# Digital-input.net
KiCad netlist of a schematic drawn in Altium Designer
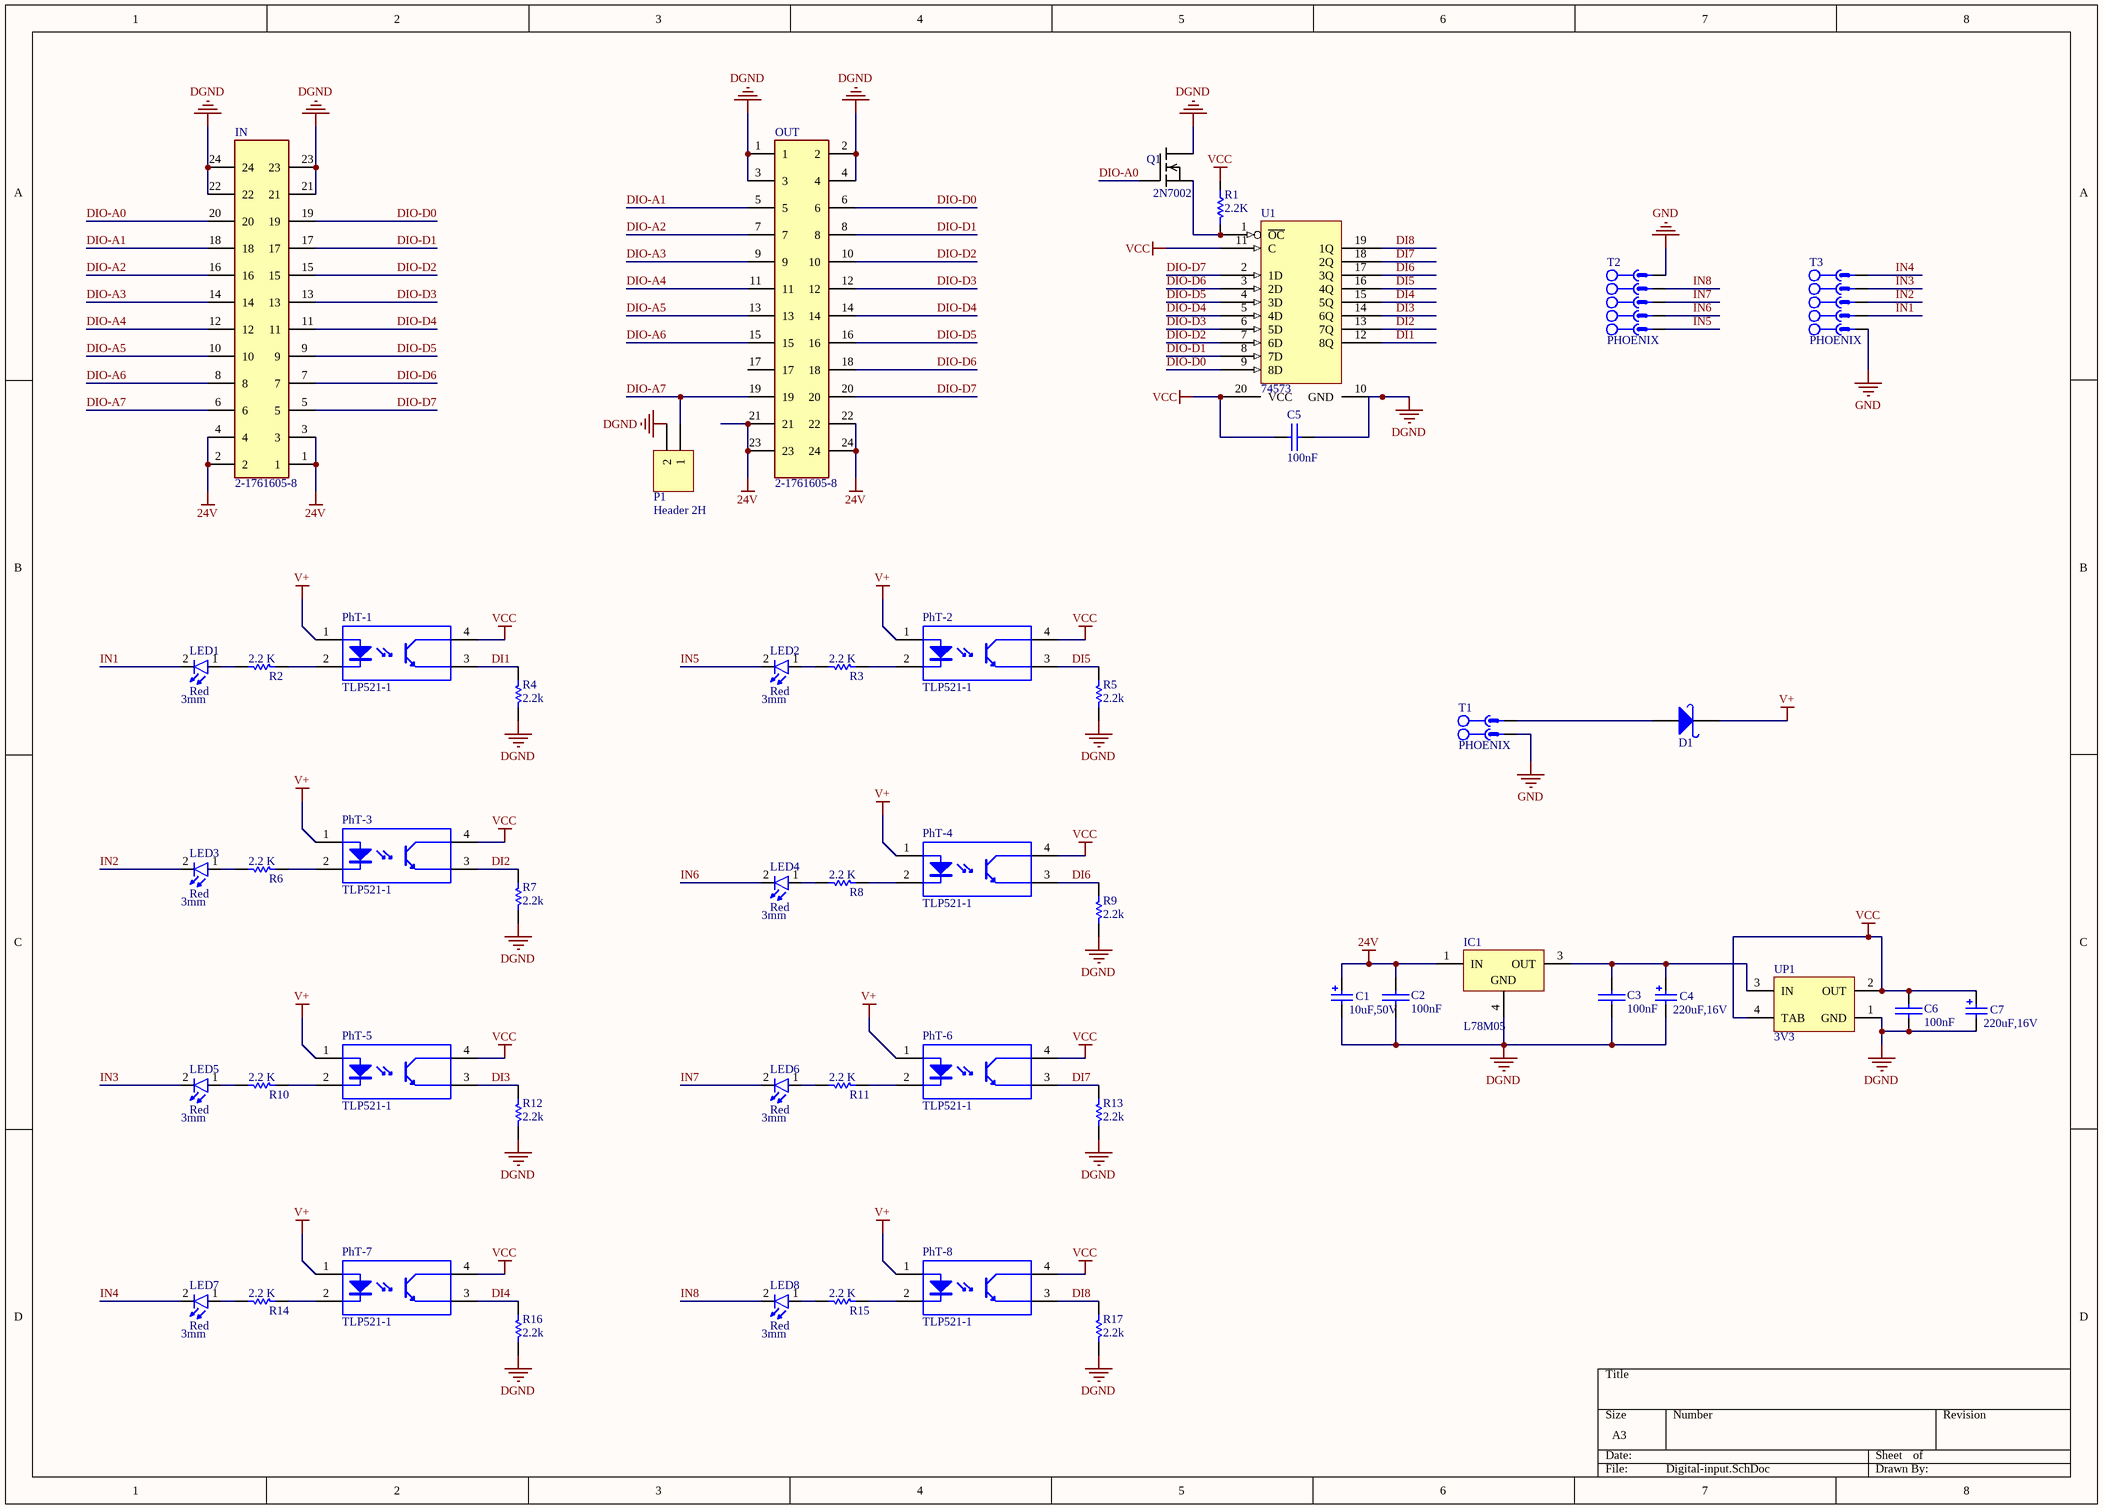
[diagram p0: Digital-input.SchDoc]

(export (version "E")
  (design (tool "Eeschema 10.0.6"))
  (components
    (comp (ref "C1")
      (value "10uF,50V")
      (footprint "WCAP-AS5H_6.3x7.7")
      (description "WCAP-AS5H SMT Aluminum Electrolytic Capacitors, D8mm x L10.5mm, 47uF, +/-20%, 50VDC")
      (fields (field (name "PART NUMBER") "865230653012") (field (name "PUBLISHER") "Wurth Elektronik"))
      (libsource (lib "Altium_WCAP-AS5H (rev19a)") (part "865230653012"))
    )
    (comp (ref "C2")
      (value "100nF")
      (footprint "SMD_CAP_0805")
      (description "Bipolar Capacitor")
      (fields (field (name "VOLTAGE") "100V") (field (name "DESIGNER") "Saeid Jorablo"))
      (libsource (lib "My_Library") (part "Cap-Bipolar"))
    )
    (comp (ref "C3")
      (value "100nF")
      (footprint "SMD_CAP_0805")
      (description "Bipolar Capacitor")
      (fields (field (name "VOLTAGE") "100V") (field (name "DESIGNER") "Saeid Jorablo"))
      (libsource (lib "My_Library") (part "Cap-Bipolar"))
    )
    (comp (ref "C4")
      (value "220uF,16V")
      (footprint "WCAP-AS5H_6.3x7.7")
      (description "WCAP-AS5H SMT Aluminum Electrolytic Capacitors, D6.3mm x L7.7mm, 100uF, +/-20%, 16VDC")
      (fields (field (name "PART NUMBER") "865230345005") (field (name "PUBLISHER") "Wurth Elektronik"))
      (libsource (lib "Altium_WCAP-AS5H (rev19a)") (part "865230345005"))
    )
    (comp (ref "C5")
      (value "100nF")
      (footprint "SMD_CAP_0805")
      (description "Bipolar Capacitor")
      (fields (field (name "VOLTAGE") "100V") (field (name "DESIGNER") "Saeid Jorablo"))
      (libsource (lib "My_Library") (part "Cap-Bipolar"))
    )
    (comp (ref "C6")
      (value "100nF")
      (footprint "SMD_CAP_0805")
      (description "Bipolar Capacitor")
      (fields (field (name "VOLTAGE") "100V") (field (name "DESIGNER") "Saeid Jorablo"))
      (libsource (lib "My_Library") (part "Cap-Bipolar"))
    )
    (comp (ref "C7")
      (value "220uF,16V")
      (footprint "WCAP-AS5H_6.3x7.7")
      (description "WCAP-AS5H SMT Aluminum Electrolytic Capacitors, D6.3mm x L7.7mm, 100uF, +/-20%, 16VDC")
      (fields (field (name "PART NUMBER") "865230345005") (field (name "PUBLISHER") "Wurth Elektronik"))
      (libsource (lib "Altium_WCAP-AS5H (rev19a)") (part "865230345005"))
    )
    (comp (ref "D1")
      (value "1n5822")
      (footprint "Diode 1N4007 SMD")
      (description "Schottky Rectifiers")
      (fields
        (field (name "MANUFACTURER") "ON Semiconductor/Fairchild")
        (field (name "DESIGNER") "Abbas Basereh")
      )
      (libsource (lib "Altium") (part "1N5822 SMD"))
    )
    (comp (ref "IC1")
      (value "L78M05")
      (footprint "TO-252")
      (description "Precision 500mA Regulator")
      (libsource (lib "My_Library") (part "L78M05"))
    )
    (comp (ref "IN")
      (value "2-1761605-8")
      (footprint "TE_2-1761605-8")
      (description "IDC LOW PRO HDR 64P RA BLUE")
      (libsource (lib "2-1761605-8") (part "2-1761605-8"))
    )
    (comp (ref "LED1")
      (value "Red")
      (footprint "LED-3mm")
      (description "LED")
      (fields
        (field (name "COLOR") "Red")
        (field (name "SIZE") "3mm")
        (field (name "DESIGNER") "Saeid Jorablo")
      )
      (libsource (lib "My_Library") (part "LED"))
    )
    (comp (ref "LED2")
      (value "Red")
      (footprint "LED-3mm")
      (description "LED")
      (fields
        (field (name "COLOR") "Red")
        (field (name "SIZE") "3mm")
        (field (name "DESIGNER") "Saeid Jorablo")
      )
      (libsource (lib "My_Library") (part "LED"))
    )
    (comp (ref "LED3")
      (value "Red")
      (footprint "LED-3mm")
      (description "LED")
      (fields
        (field (name "COLOR") "Red")
        (field (name "SIZE") "3mm")
        (field (name "DESIGNER") "Saeid Jorablo")
      )
      (libsource (lib "My_Library") (part "LED"))
    )
    (comp (ref "LED4")
      (value "Red")
      (footprint "LED-3mm")
      (description "LED")
      (fields
        (field (name "COLOR") "Red")
        (field (name "SIZE") "3mm")
        (field (name "DESIGNER") "Saeid Jorablo")
      )
      (libsource (lib "My_Library") (part "LED"))
    )
    (comp (ref "LED5")
      (value "Red")
      (footprint "LED-3mm")
      (description "LED")
      (fields
        (field (name "COLOR") "Red")
        (field (name "SIZE") "3mm")
        (field (name "DESIGNER") "Saeid Jorablo")
      )
      (libsource (lib "My_Library") (part "LED"))
    )
    (comp (ref "LED6")
      (value "Red")
      (footprint "LED-3mm")
      (description "LED")
      (fields
        (field (name "COLOR") "Red")
        (field (name "SIZE") "3mm")
        (field (name "DESIGNER") "Saeid Jorablo")
      )
      (libsource (lib "My_Library") (part "LED"))
    )
    (comp (ref "LED7")
      (value "Red")
      (footprint "LED-3mm")
      (description "LED")
      (fields
        (field (name "COLOR") "Red")
        (field (name "SIZE") "3mm")
        (field (name "DESIGNER") "Saeid Jorablo")
      )
      (libsource (lib "My_Library") (part "LED"))
    )
    (comp (ref "LED8")
      (value "Red")
      (footprint "LED-3mm")
      (description "LED")
      (fields
        (field (name "COLOR") "Red")
        (field (name "SIZE") "3mm")
        (field (name "DESIGNER") "Saeid Jorablo")
      )
      (libsource (lib "My_Library") (part "LED"))
    )
    (comp (ref "OUT")
      (value "2-1761605-8")
      (footprint "TE_2-1761605-8")
      (description "IDC LOW PRO HDR 64P RA BLUE")
      (libsource (lib "") (part "2-1761605-8_1"))
    )
    (comp (ref "P1")
      (value "Header 2H")
      (footprint "HDR1X2H")
      (description "Header, 2-Pin, Right Angle")
      (fields (field (name "PUBLISHER") "Altium Limited"))
      (libsource (lib "Miscellaneous Connectors") (part "Header 2H"))
    )
    (comp (ref "PhT-1")
      (value "TLP521-1")
      (footprint "PCBComponent_1")
      (libsource (lib "TLP521-1") (part "TLP521-1"))
    )
    (comp (ref "PhT-2")
      (value "TLP521-1")
      (footprint "PCBComponent_1")
      (libsource (lib "TLP521-1") (part "TLP521-1"))
    )
    (comp (ref "PhT-3")
      (value "TLP521-1")
      (footprint "PCBComponent_1")
      (libsource (lib "TLP521-1") (part "TLP521-1"))
    )
    (comp (ref "PhT-4")
      (value "TLP521-1")
      (footprint "PCBComponent_1")
      (libsource (lib "TLP521-1") (part "TLP521-1"))
    )
    (comp (ref "PhT-5")
      (value "TLP521-1")
      (footprint "PCBComponent_1")
      (libsource (lib "TLP521-1") (part "TLP521-1"))
    )
    (comp (ref "PhT-6")
      (value "TLP521-1")
      (footprint "PCBComponent_1")
      (libsource (lib "TLP521-1") (part "TLP521-1"))
    )
    (comp (ref "PhT-7")
      (value "TLP521-1")
      (footprint "PCBComponent_1")
      (libsource (lib "TLP521-1") (part "TLP521-1"))
    )
    (comp (ref "PhT-8")
      (value "TLP521-1")
      (footprint "PCBComponent_1")
      (libsource (lib "TLP521-1") (part "TLP521-1"))
    )
    (comp (ref "Q1")
      (value "2N7002")
      (footprint "*SOT23")
      (description "Transistor NPN Mos 2N7002 SILICONIX miliampere=100 V=60 SOt23")
      (fields (field (name "MF") "STMicroelectronics"))
      (libsource (lib "2N7002") (part "2N7002"))
    )
    (comp (ref "R1")
      (value "2.2K")
      (footprint "RES 0805 (2012X06L)")
      (description "Resistor")
      (fields (field (name "TOLERANCE") "5%") (field (name "POWER") "1/8 W"))
      (libsource (lib "My_Library") (part "Resistor"))
    )
    (comp (ref "R2")
      (value "2.2 K")
      (footprint "RES 1206 (3216X08L)")
      (description "Semiconductor Resistor")
      (fields (field (name "PUBLISHER") "Altium Limited"))
      (libsource (lib "ZS_RESISTOR") (part "RESISTOR"))
    )
    (comp (ref "R3")
      (value "2.2 K")
      (footprint "RES 1206 (3216X08L)")
      (description "Semiconductor Resistor")
      (fields (field (name "PUBLISHER") "Altium Limited"))
      (libsource (lib "ZS_RESISTOR") (part "RESISTOR"))
    )
    (comp (ref "R4")
      (value "2.2k")
      (footprint "RES 1206 (3216X08L)")
      (description "Semiconductor Resistor")
      (fields (field (name "PUBLISHER") "Altium Limited"))
      (libsource (lib "ZS_RESISTOR") (part "RESISTOR"))
    )
    (comp (ref "R5")
      (value "2.2k")
      (footprint "RES 1206 (3216X08L)")
      (description "Semiconductor Resistor")
      (fields (field (name "PUBLISHER") "Altium Limited"))
      (libsource (lib "ZS_RESISTOR") (part "RESISTOR"))
    )
    (comp (ref "R6")
      (value "2.2 K")
      (footprint "RES 1206 (3216X08L)")
      (description "Semiconductor Resistor")
      (fields (field (name "PUBLISHER") "Altium Limited"))
      (libsource (lib "ZS_RESISTOR") (part "RESISTOR"))
    )
    (comp (ref "R7")
      (value "2.2k")
      (footprint "RES 1206 (3216X08L)")
      (description "Semiconductor Resistor")
      (fields (field (name "PUBLISHER") "Altium Limited"))
      (libsource (lib "ZS_RESISTOR") (part "RESISTOR"))
    )
    (comp (ref "R8")
      (value "2.2 K")
      (footprint "RES 1206 (3216X08L)")
      (description "Semiconductor Resistor")
      (fields (field (name "PUBLISHER") "Altium Limited"))
      (libsource (lib "ZS_RESISTOR") (part "RESISTOR"))
    )
    (comp (ref "R9")
      (value "2.2k")
      (footprint "RES 1206 (3216X08L)")
      (description "Semiconductor Resistor")
      (fields (field (name "PUBLISHER") "Altium Limited"))
      (libsource (lib "ZS_RESISTOR") (part "RESISTOR"))
    )
    (comp (ref "R10")
      (value "2.2 K")
      (footprint "RES 1206 (3216X08L)")
      (description "Semiconductor Resistor")
      (fields (field (name "PUBLISHER") "Altium Limited"))
      (libsource (lib "ZS_RESISTOR") (part "RESISTOR"))
    )
    (comp (ref "R11")
      (value "2.2 K")
      (footprint "RES 1206 (3216X08L)")
      (description "Semiconductor Resistor")
      (fields (field (name "PUBLISHER") "Altium Limited"))
      (libsource (lib "ZS_RESISTOR") (part "RESISTOR"))
    )
    (comp (ref "R12")
      (value "2.2k")
      (footprint "RES 1206 (3216X08L)")
      (description "Semiconductor Resistor")
      (fields (field (name "PUBLISHER") "Altium Limited"))
      (libsource (lib "ZS_RESISTOR") (part "RESISTOR"))
    )
    (comp (ref "R13")
      (value "2.2k")
      (footprint "RES 1206 (3216X08L)")
      (description "Semiconductor Resistor")
      (fields (field (name "PUBLISHER") "Altium Limited"))
      (libsource (lib "ZS_RESISTOR") (part "RESISTOR"))
    )
    (comp (ref "R14")
      (value "2.2 K")
      (footprint "RES 1206 (3216X08L)")
      (description "Semiconductor Resistor")
      (fields (field (name "PUBLISHER") "Altium Limited"))
      (libsource (lib "ZS_RESISTOR") (part "RESISTOR"))
    )
    (comp (ref "R15")
      (value "2.2 K")
      (footprint "RES 1206 (3216X08L)")
      (description "Semiconductor Resistor")
      (fields (field (name "PUBLISHER") "Altium Limited"))
      (libsource (lib "ZS_RESISTOR") (part "RESISTOR"))
    )
    (comp (ref "R16")
      (value "2.2k")
      (footprint "RES 1206 (3216X08L)")
      (description "Semiconductor Resistor")
      (fields (field (name "PUBLISHER") "Altium Limited"))
      (libsource (lib "ZS_RESISTOR") (part "RESISTOR"))
    )
    (comp (ref "R17")
      (value "2.2k")
      (footprint "RES 1206 (3216X08L)")
      (description "Semiconductor Resistor")
      (fields (field (name "PUBLISHER") "Altium Limited"))
      (libsource (lib "ZS_RESISTOR") (part "RESISTOR"))
    )
    (comp (ref "T1")
      (value "PHOENIX")
      (footprint "MSTB 2,5/2-G-5,08")
      (description "2 Pitch: 5.08 mm Color: green Contact surface: Tin Assembly")
      (fields
        (field (name "MANUFACTURER") "PHOENIX CONTACT")
        (field (name "VOLTAGE") "320 V")
        (field (name "DESIGNER") "ABBAS BASEREH")
      )
      (libsource (lib "Altium") (part "CON_Phoenix_MSTB_02"))
    )
    (comp (ref "T2")
      (value "PHOENIX")
      (footprint "MSTB 2,5/5-G-5,08")
      (description "5 Pitch: 5.08 mm Color: green Contact surface: Tin Assembly")
      (fields
        (field (name "MANUFACTURER") "PHOENIX CONTACT")
        (field (name "VOLTAGE") "320 V")
        (field (name "DESIGNER") "ABBAS BASEREH")
      )
      (libsource (lib "Altium") (part "CON_Phoenix_MSTB_05"))
    )
    (comp (ref "T3")
      (value "PHOENIX")
      (footprint "MSTB 2,5/5-G-5,08")
      (description "5 Pitch: 5.08 mm Color: green Contact surface: Tin Assembly")
      (fields
        (field (name "MANUFACTURER") "PHOENIX CONTACT")
        (field (name "VOLTAGE") "320 V")
        (field (name "DESIGNER") "ABBAS BASEREH")
      )
      (libsource (lib "Altium") (part "CON_Phoenix_MSTB_05"))
    )
    (comp (ref "U1")
      (value "74573")
      (footprint "SO20_M")
      (description "OCTAL D-TYPE TRANSPARENT LCH")
      (libsource (lib "Altium library (www.AVRelec.com)") (part "74573"))
    )
    (comp (ref "UP1")
      (value "3V3")
      (footprint "SOT223")
      (description "x.x Volt, 800mA Low-Dropout Linear Regulator, 4-pin SOT-223")
      (fields (field (name "DESIGNER") "Ali Hafizi"))
      (libsource (lib "Altium") (part "AMS1117-x.x"))
    )
  )
  (nets
    (net (code "1") (name "/DI1") (class "Default")
      (node (ref "PhT-1") (pin "3") (pinfunction "E_3") (pintype "passive"))
      (node (ref "R4") (pin "1") (pinfunction "1_1") (pintype "passive"))
      (node (ref "U1") (pin "12") (pinfunction "8Q_12") (pintype "tri_state"))
    )
    (net (code "2") (name "/DI2") (class "Default")
      (node (ref "PhT-3") (pin "3") (pinfunction "E_3") (pintype "passive"))
      (node (ref "R7") (pin "1") (pinfunction "1_1") (pintype "passive"))
      (node (ref "U1") (pin "13") (pinfunction "7Q_13") (pintype "tri_state"))
    )
    (net (code "3") (name "/DI3") (class "Default")
      (node (ref "PhT-5") (pin "3") (pinfunction "E_3") (pintype "passive"))
      (node (ref "R12") (pin "1") (pinfunction "1_1") (pintype "passive"))
      (node (ref "U1") (pin "14") (pinfunction "6Q_14") (pintype "tri_state"))
    )
    (net (code "4") (name "/DI4") (class "Default")
      (node (ref "PhT-7") (pin "3") (pinfunction "E_3") (pintype "passive"))
      (node (ref "R16") (pin "1") (pinfunction "1_1") (pintype "passive"))
      (node (ref "U1") (pin "15") (pinfunction "5Q_15") (pintype "tri_state"))
    )
    (net (code "5") (name "/DI5") (class "Default")
      (node (ref "PhT-2") (pin "3") (pinfunction "E_3") (pintype "passive"))
      (node (ref "R5") (pin "1") (pinfunction "1_1") (pintype "passive"))
      (node (ref "U1") (pin "16") (pinfunction "4Q_16") (pintype "tri_state"))
    )
    (net (code "6") (name "/DI6") (class "Default")
      (node (ref "PhT-4") (pin "3") (pinfunction "E_3") (pintype "passive"))
      (node (ref "R9") (pin "1") (pinfunction "1_1") (pintype "passive"))
      (node (ref "U1") (pin "17") (pinfunction "3Q_17") (pintype "tri_state"))
    )
    (net (code "7") (name "/DI7") (class "Default")
      (node (ref "PhT-6") (pin "3") (pinfunction "E_3") (pintype "passive"))
      (node (ref "R13") (pin "1") (pinfunction "1_1") (pintype "passive"))
      (node (ref "U1") (pin "18") (pinfunction "2Q_18") (pintype "tri_state"))
    )
    (net (code "8") (name "/DI8") (class "Default")
      (node (ref "PhT-8") (pin "3") (pinfunction "E_3") (pintype "passive"))
      (node (ref "R17") (pin "1") (pinfunction "1_1") (pintype "passive"))
      (node (ref "U1") (pin "19") (pinfunction "1Q_19") (pintype "tri_state"))
    )
    (net (code "9") (name "/DIO-A0") (class "Default")
      (node (ref "IN") (pin "20") (pinfunction "20_20") (pintype "passive"))
      (node (ref "Q1") (pin "1") (pinfunction "G_1") (pintype "passive"))
    )
    (net (code "10") (name "/DIO-A1") (class "Default")
      (node (ref "IN") (pin "18") (pinfunction "18_18") (pintype "passive"))
      (node (ref "OUT") (pin "5") (pinfunction "5_5") (pintype "passive"))
    )
    (net (code "11") (name "/DIO-A2") (class "Default")
      (node (ref "IN") (pin "16") (pinfunction "16_16") (pintype "passive"))
      (node (ref "OUT") (pin "7") (pinfunction "7_7") (pintype "passive"))
    )
    (net (code "12") (name "/DIO-A3") (class "Default")
      (node (ref "IN") (pin "14") (pinfunction "14_14") (pintype "passive"))
      (node (ref "OUT") (pin "9") (pinfunction "9_9") (pintype "passive"))
    )
    (net (code "13") (name "/DIO-A4") (class "Default")
      (node (ref "IN") (pin "12") (pinfunction "12_12") (pintype "passive"))
      (node (ref "OUT") (pin "11") (pinfunction "11_11") (pintype "passive"))
    )
    (net (code "14") (name "/DIO-A5") (class "Default")
      (node (ref "IN") (pin "10") (pinfunction "10_10") (pintype "passive"))
      (node (ref "OUT") (pin "13") (pinfunction "13_13") (pintype "passive"))
    )
    (net (code "15") (name "/DIO-A6") (class "Default")
      (node (ref "IN") (pin "8") (pinfunction "8_8") (pintype "passive"))
      (node (ref "OUT") (pin "15") (pinfunction "15_15") (pintype "passive"))
    )
    (net (code "16") (name "/DIO-A7") (class "Default")
      (node (ref "IN") (pin "6") (pinfunction "6_6") (pintype "passive"))
      (node (ref "OUT") (pin "19") (pinfunction "19_19") (pintype "passive"))
      (node (ref "P1") (pin "1") (pinfunction "1_1") (pintype "passive"))
    )
    (net (code "17") (name "/DIO-D0") (class "Default")
      (node (ref "IN") (pin "19") (pinfunction "19_19") (pintype "passive"))
      (node (ref "OUT") (pin "6") (pinfunction "6_6") (pintype "passive"))
      (node (ref "U1") (pin "9") (pinfunction "8D_9") (pintype "input"))
    )
    (net (code "18") (name "/DIO-D1") (class "Default")
      (node (ref "IN") (pin "17") (pinfunction "17_17") (pintype "passive"))
      (node (ref "OUT") (pin "8") (pinfunction "8_8") (pintype "passive"))
      (node (ref "U1") (pin "8") (pinfunction "7D_8") (pintype "input"))
    )
    (net (code "19") (name "/DIO-D2") (class "Default")
      (node (ref "IN") (pin "15") (pinfunction "15_15") (pintype "passive"))
      (node (ref "OUT") (pin "10") (pinfunction "10_10") (pintype "passive"))
      (node (ref "U1") (pin "7") (pinfunction "6D_7") (pintype "input"))
    )
    (net (code "20") (name "/DIO-D3") (class "Default")
      (node (ref "IN") (pin "13") (pinfunction "13_13") (pintype "passive"))
      (node (ref "OUT") (pin "12") (pinfunction "12_12") (pintype "passive"))
      (node (ref "U1") (pin "6") (pinfunction "5D_6") (pintype "input"))
    )
    (net (code "21") (name "/DIO-D4") (class "Default")
      (node (ref "IN") (pin "11") (pinfunction "11_11") (pintype "passive"))
      (node (ref "OUT") (pin "14") (pinfunction "14_14") (pintype "passive"))
      (node (ref "U1") (pin "5") (pinfunction "4D_5") (pintype "input"))
    )
    (net (code "22") (name "/DIO-D5") (class "Default")
      (node (ref "IN") (pin "9") (pinfunction "9_9") (pintype "passive"))
      (node (ref "OUT") (pin "16") (pinfunction "16_16") (pintype "passive"))
      (node (ref "U1") (pin "4") (pinfunction "3D_4") (pintype "input"))
    )
    (net (code "23") (name "/DIO-D6") (class "Default")
      (node (ref "IN") (pin "7") (pinfunction "7_7") (pintype "passive"))
      (node (ref "OUT") (pin "18") (pinfunction "18_18") (pintype "passive"))
      (node (ref "U1") (pin "3") (pinfunction "2D_3") (pintype "input"))
    )
    (net (code "24") (name "/DIO-D7") (class "Default")
      (node (ref "IN") (pin "5") (pinfunction "5_5") (pintype "passive"))
      (node (ref "OUT") (pin "20") (pinfunction "20_20") (pintype "passive"))
      (node (ref "U1") (pin "2") (pinfunction "1D_2") (pintype "input"))
    )
    (net (code "25") (name "/IN1") (class "Default")
      (node (ref "LED1") (pin "2") (pinfunction "K_2") (pintype "passive"))
      (node (ref "T3") (pin "2") (pinfunction "2_2") (pintype "passive"))
    )
    (net (code "26") (name "/IN2") (class "Default")
      (node (ref "LED3") (pin "2") (pinfunction "K_2") (pintype "passive"))
      (node (ref "T3") (pin "3") (pinfunction "3_3") (pintype "passive"))
    )
    (net (code "27") (name "/IN3") (class "Default")
      (node (ref "LED5") (pin "2") (pinfunction "K_2") (pintype "passive"))
      (node (ref "T3") (pin "4") (pinfunction "4_4") (pintype "passive"))
    )
    (net (code "28") (name "/IN4") (class "Default")
      (node (ref "LED7") (pin "2") (pinfunction "K_2") (pintype "passive"))
      (node (ref "T3") (pin "5") (pinfunction "5_5") (pintype "passive"))
    )
    (net (code "29") (name "/IN5") (class "Default")
      (node (ref "LED2") (pin "2") (pinfunction "K_2") (pintype "passive"))
      (node (ref "T2") (pin "1") (pinfunction "1_1") (pintype "passive"))
    )
    (net (code "30") (name "/IN6") (class "Default")
      (node (ref "LED4") (pin "2") (pinfunction "K_2") (pintype "passive"))
      (node (ref "T2") (pin "2") (pinfunction "2_2") (pintype "passive"))
    )
    (net (code "31") (name "/IN7") (class "Default")
      (node (ref "LED6") (pin "2") (pinfunction "K_2") (pintype "passive"))
      (node (ref "T2") (pin "3") (pinfunction "3_3") (pintype "passive"))
    )
    (net (code "32") (name "/IN8") (class "Default")
      (node (ref "LED8") (pin "2") (pinfunction "K_2") (pintype "passive"))
      (node (ref "T2") (pin "4") (pinfunction "4_4") (pintype "passive"))
    )
    (net (code "33") (name "24V") (class "Default")
      (node (ref "C1") (pin "2") (pinfunction "P_2") (pintype "passive"))
      (node (ref "C2") (pin "2") (pinfunction "-_2") (pintype "passive"))
      (node (ref "IC1") (pin "1") (pinfunction "IN_1") (pintype "power_in"))
      (node (ref "IN") (pin "1") (pinfunction "1_1") (pintype "passive"))
      (node (ref "IN") (pin "2") (pinfunction "2_2") (pintype "passive"))
      (node (ref "IN") (pin "3") (pinfunction "3_3") (pintype "passive"))
      (node (ref "IN") (pin "4") (pinfunction "4_4") (pintype "passive"))
      (node (ref "OUT") (pin "21") (pinfunction "21_21") (pintype "passive"))
      (node (ref "OUT") (pin "22") (pinfunction "22_22") (pintype "passive"))
      (node (ref "OUT") (pin "23") (pinfunction "23_23") (pintype "passive"))
      (node (ref "OUT") (pin "24") (pinfunction "24_24") (pintype "passive"))
    )
    (net (code "34") (name "DGND") (class "Default")
      (node (ref "C1") (pin "1") (pinfunction "N_1") (pintype "passive"))
      (node (ref "C2") (pin "1") (pinfunction "+_1") (pintype "passive"))
      (node (ref "C3") (pin "1") (pinfunction "+_1") (pintype "passive"))
      (node (ref "C4") (pin "1") (pinfunction "N_1") (pintype "passive"))
      (node (ref "C5") (pin "1") (pinfunction "+_1") (pintype "passive"))
      (node (ref "C6") (pin "1") (pinfunction "+_1") (pintype "passive"))
      (node (ref "C7") (pin "1") (pinfunction "N_1") (pintype "passive"))
      (node (ref "IC1") (pin "4") (pinfunction "GND_4") (pintype "power_in"))
      (node (ref "IN") (pin "21") (pinfunction "21_21") (pintype "passive"))
      (node (ref "IN") (pin "22") (pinfunction "22_22") (pintype "passive"))
      (node (ref "IN") (pin "23") (pinfunction "23_23") (pintype "passive"))
      (node (ref "IN") (pin "24") (pinfunction "24_24") (pintype "passive"))
      (node (ref "OUT") (pin "1") (pinfunction "1_1") (pintype "passive"))
      (node (ref "OUT") (pin "2") (pinfunction "2_2") (pintype "passive"))
      (node (ref "OUT") (pin "3") (pinfunction "3_3") (pintype "passive"))
      (node (ref "OUT") (pin "4") (pinfunction "4_4") (pintype "passive"))
      (node (ref "P1") (pin "2") (pinfunction "2_2") (pintype "passive"))
      (node (ref "Q1") (pin "3") (pinfunction "D_3") (pintype "passive"))
      (node (ref "R12") (pin "2") (pinfunction "2_2") (pintype "passive"))
      (node (ref "R13") (pin "2") (pinfunction "2_2") (pintype "passive"))
      (node (ref "R16") (pin "2") (pinfunction "2_2") (pintype "passive"))
      (node (ref "R17") (pin "2") (pinfunction "2_2") (pintype "passive"))
      (node (ref "R4") (pin "2") (pinfunction "2_2") (pintype "passive"))
      (node (ref "R5") (pin "2") (pinfunction "2_2") (pintype "passive"))
      (node (ref "R7") (pin "2") (pinfunction "2_2") (pintype "passive"))
      (node (ref "R9") (pin "2") (pinfunction "2_2") (pintype "passive"))
      (node (ref "T1") (pin "1") (pinfunction "1_1") (pintype "passive"))
      (node (ref "T2") (pin "5") (pinfunction "5_5") (pintype "passive"))
      (node (ref "T3") (pin "1") (pinfunction "1_1") (pintype "passive"))
      (node (ref "U1") (pin "10") (pinfunction "GND_10") (pintype "power_in"))
      (node (ref "UP1") (pin "1") (pinfunction "GND_1") (pintype "power_in"))
    )
    (net (code "35") (name "Net-(C3--)") (class "Default")
      (node (ref "C3") (pin "2") (pinfunction "-_2") (pintype "passive"))
      (node (ref "C4") (pin "2") (pinfunction "P_2") (pintype "passive"))
      (node (ref "IC1") (pin "3") (pinfunction "OUT_3") (pintype "power_in"))
      (node (ref "UP1") (pin "3") (pinfunction "IN_3") (pintype "power_in"))
    )
    (net (code "36") (name "Net-(D1-A)") (class "Default")
      (node (ref "D1") (pin "1") (pinfunction "A_1") (pintype "passive"))
      (node (ref "T1") (pin "2") (pinfunction "2_2") (pintype "passive"))
    )
    (net (code "37") (name "Net-(LED1-A)") (class "Default")
      (node (ref "LED1") (pin "1") (pinfunction "A_1") (pintype "passive"))
      (node (ref "R2") (pin "2") (pinfunction "2_2") (pintype "passive"))
    )
    (net (code "38") (name "Net-(LED2-A)") (class "Default")
      (node (ref "LED2") (pin "1") (pinfunction "A_1") (pintype "passive"))
      (node (ref "R3") (pin "2") (pinfunction "2_2") (pintype "passive"))
    )
    (net (code "39") (name "Net-(LED3-A)") (class "Default")
      (node (ref "LED3") (pin "1") (pinfunction "A_1") (pintype "passive"))
      (node (ref "R6") (pin "2") (pinfunction "2_2") (pintype "passive"))
    )
    (net (code "40") (name "Net-(LED4-A)") (class "Default")
      (node (ref "LED4") (pin "1") (pinfunction "A_1") (pintype "passive"))
      (node (ref "R8") (pin "2") (pinfunction "2_2") (pintype "passive"))
    )
    (net (code "41") (name "Net-(LED5-A)") (class "Default")
      (node (ref "LED5") (pin "1") (pinfunction "A_1") (pintype "passive"))
      (node (ref "R10") (pin "2") (pinfunction "2_2") (pintype "passive"))
    )
    (net (code "42") (name "Net-(LED6-A)") (class "Default")
      (node (ref "LED6") (pin "1") (pinfunction "A_1") (pintype "passive"))
      (node (ref "R11") (pin "2") (pinfunction "2_2") (pintype "passive"))
    )
    (net (code "43") (name "Net-(LED7-A)") (class "Default")
      (node (ref "LED7") (pin "1") (pinfunction "A_1") (pintype "passive"))
      (node (ref "R14") (pin "2") (pinfunction "2_2") (pintype "passive"))
    )
    (net (code "44") (name "Net-(LED8-A)") (class "Default")
      (node (ref "LED8") (pin "1") (pinfunction "A_1") (pintype "passive"))
      (node (ref "R15") (pin "2") (pinfunction "2_2") (pintype "passive"))
    )
    (net (code "45") (name "Net-(PhT-1-K)") (class "Default")
      (node (ref "PhT-1") (pin "2") (pinfunction "K_2") (pintype "passive"))
      (node (ref "R2") (pin "1") (pinfunction "1_1") (pintype "passive"))
    )
    (net (code "46") (name "Net-(PhT-2-K)") (class "Default")
      (node (ref "PhT-2") (pin "2") (pinfunction "K_2") (pintype "passive"))
      (node (ref "R3") (pin "1") (pinfunction "1_1") (pintype "passive"))
    )
    (net (code "47") (name "Net-(PhT-3-K)") (class "Default")
      (node (ref "PhT-3") (pin "2") (pinfunction "K_2") (pintype "passive"))
      (node (ref "R6") (pin "1") (pinfunction "1_1") (pintype "passive"))
    )
    (net (code "48") (name "Net-(PhT-4-K)") (class "Default")
      (node (ref "PhT-4") (pin "2") (pinfunction "K_2") (pintype "passive"))
      (node (ref "R8") (pin "1") (pinfunction "1_1") (pintype "passive"))
    )
    (net (code "49") (name "Net-(PhT-5-K)") (class "Default")
      (node (ref "PhT-5") (pin "2") (pinfunction "K_2") (pintype "passive"))
      (node (ref "R10") (pin "1") (pinfunction "1_1") (pintype "passive"))
    )
    (net (code "50") (name "Net-(PhT-6-K)") (class "Default")
      (node (ref "PhT-6") (pin "2") (pinfunction "K_2") (pintype "passive"))
      (node (ref "R11") (pin "1") (pinfunction "1_1") (pintype "passive"))
    )
    (net (code "51") (name "Net-(PhT-7-K)") (class "Default")
      (node (ref "PhT-7") (pin "2") (pinfunction "K_2") (pintype "passive"))
      (node (ref "R14") (pin "1") (pinfunction "1_1") (pintype "passive"))
    )
    (net (code "52") (name "Net-(PhT-8-K)") (class "Default")
      (node (ref "PhT-8") (pin "2") (pinfunction "K_2") (pintype "passive"))
      (node (ref "R15") (pin "1") (pinfunction "1_1") (pintype "passive"))
    )
    (net (code "53") (name "Net-(Q1-S)") (class "Default")
      (node (ref "Q1") (pin "2") (pinfunction "S_2") (pintype "passive"))
      (node (ref "R1") (pin "2") (pinfunction "2_2") (pintype "passive"))
      (node (ref "U1") (pin "1") (pinfunction "~{OC}_1") (pintype "input"))
    )
    (net (code "54") (name "V+") (class "Default")
      (node (ref "D1") (pin "2") (pinfunction "K_2") (pintype "passive"))
      (node (ref "PhT-1") (pin "1") (pinfunction "A_1") (pintype "passive"))
      (node (ref "PhT-2") (pin "1") (pinfunction "A_1") (pintype "passive"))
      (node (ref "PhT-3") (pin "1") (pinfunction "A_1") (pintype "passive"))
      (node (ref "PhT-4") (pin "1") (pinfunction "A_1") (pintype "passive"))
      (node (ref "PhT-5") (pin "1") (pinfunction "A_1") (pintype "passive"))
      (node (ref "PhT-6") (pin "1") (pinfunction "A_1") (pintype "passive"))
      (node (ref "PhT-7") (pin "1") (pinfunction "A_1") (pintype "passive"))
      (node (ref "PhT-8") (pin "1") (pinfunction "A_1") (pintype "passive"))
    )
    (net (code "55") (name "VCC") (class "Default")
      (node (ref "C5") (pin "2") (pinfunction "-_2") (pintype "passive"))
      (node (ref "C6") (pin "2") (pinfunction "-_2") (pintype "passive"))
      (node (ref "C7") (pin "2") (pinfunction "P_2") (pintype "passive"))
      (node (ref "PhT-1") (pin "4") (pinfunction "C_4") (pintype "passive"))
      (node (ref "PhT-2") (pin "4") (pinfunction "C_4") (pintype "passive"))
      (node (ref "PhT-3") (pin "4") (pinfunction "C_4") (pintype "passive"))
      (node (ref "PhT-4") (pin "4") (pinfunction "C_4") (pintype "passive"))
      (node (ref "PhT-5") (pin "4") (pinfunction "C_4") (pintype "passive"))
      (node (ref "PhT-6") (pin "4") (pinfunction "C_4") (pintype "passive"))
      (node (ref "PhT-7") (pin "4") (pinfunction "C_4") (pintype "passive"))
      (node (ref "PhT-8") (pin "4") (pinfunction "C_4") (pintype "passive"))
      (node (ref "R1") (pin "1") (pinfunction "1_1") (pintype "passive"))
      (node (ref "U1") (pin "11") (pinfunction "C_11") (pintype "input"))
      (node (ref "U1") (pin "20") (pinfunction "VCC_20") (pintype "power_in"))
      (node (ref "UP1") (pin "2") (pinfunction "OUT_2") (pintype "power_in"))
      (node (ref "UP1") (pin "4") (pinfunction "TAB_4") (pintype "power_in"))
    )
    (net (code "56") (name "unconnected-(OUT-Pad17)") (class "Default")
      (node (ref "OUT") (pin "17") (pinfunction "17_17") (pintype "passive"))
    )
  )
)
